# power_supplies.net
KiCad netlist of a schematic drawn in Altium Designer
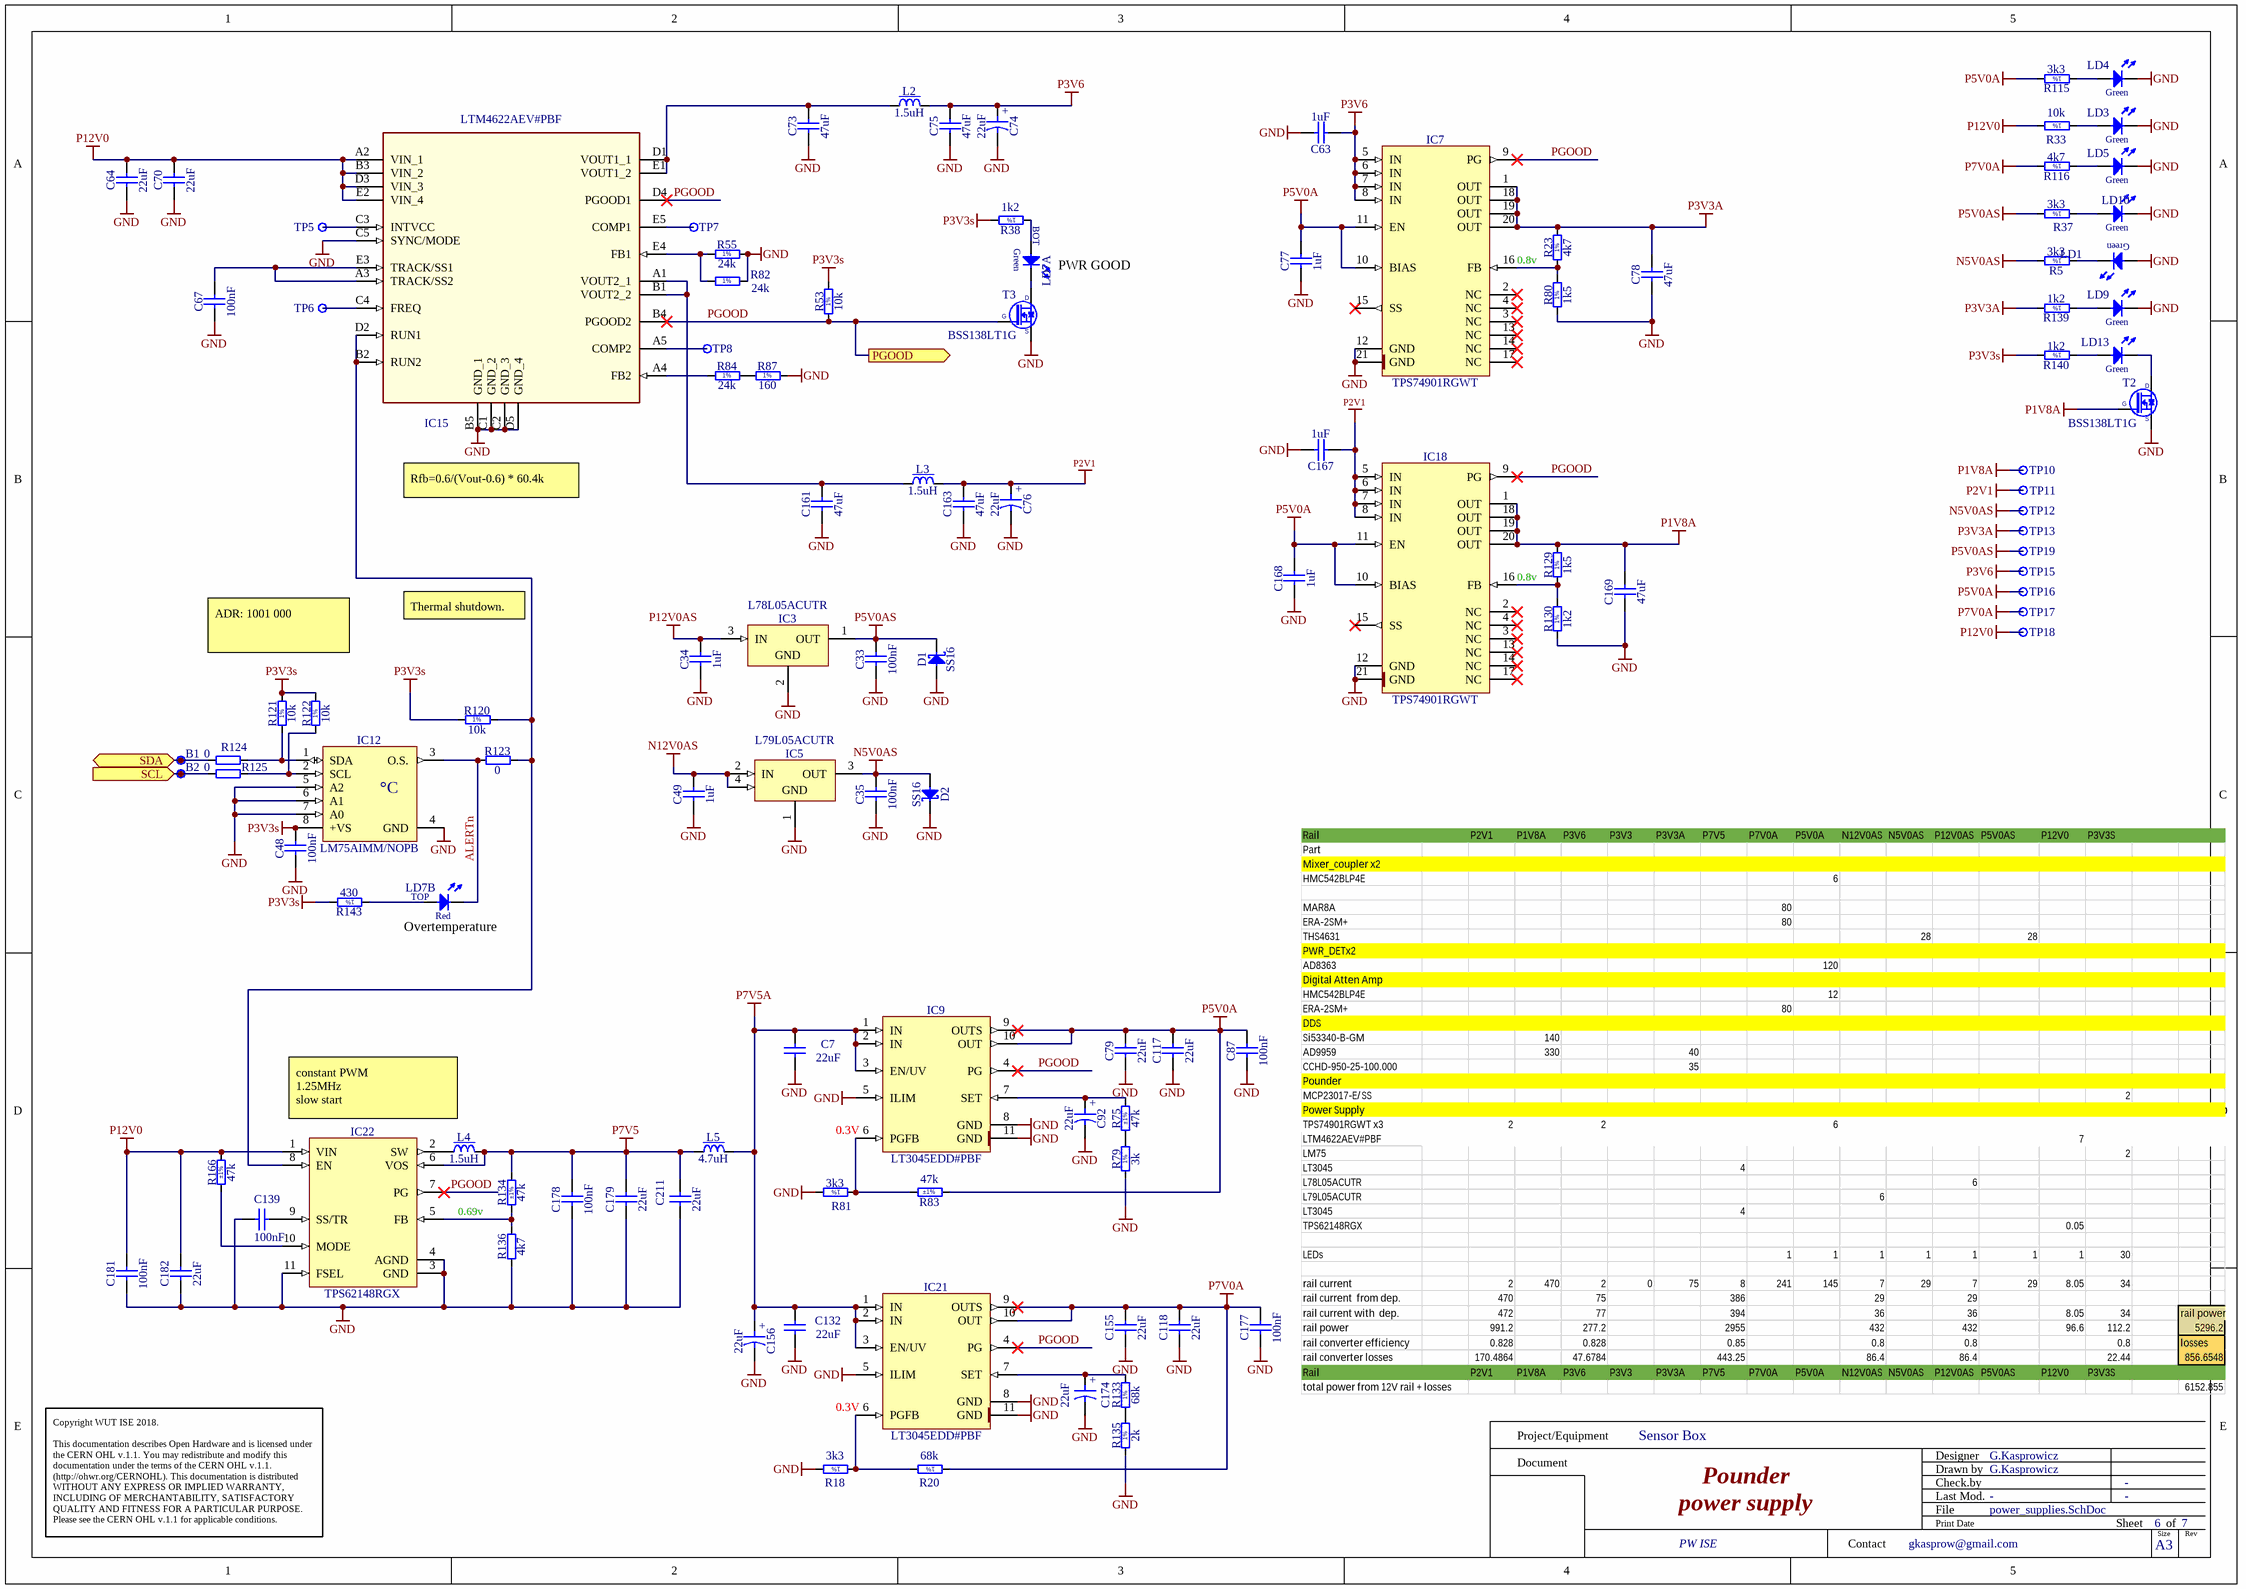
[diagram p0: power_supplies.SchDoc]

(export (version "E")
  (design (tool "Eeschema 10.0.6"))
  (components
    (comp (ref "B1")
      (value "SMD Pad")
      (footprint "C100")
      (description "Through Hole Pad")
      (fields (field (name "PART NUMBER") "SMD_PAD_D1MM") (field (name "AUTHOR") "CERN DEM JLC"))
      (libsource (lib "Eletro-mechanical") (part "Single SMD Pad (Round)"))
    )
    (comp (ref "B2")
      (value "SMD Pad")
      (footprint "C100")
      (description "Through Hole Pad")
      (fields (field (name "PART NUMBER") "SMD_PAD_D1MM") (field (name "AUTHOR") "CERN DEM JLC"))
      (libsource (lib "Eletro-mechanical") (part "Single SMD Pad (Round)"))
    )
    (comp (ref "C7")
      (value "22uF")
      (footprint "CAPC2012X135N")
      (description "Non-polarised capacitor")
      (fields
        (field (name "PART NUMBER") "CC0805_22UF_16V_10%_X5R")
        (field (name "VOLTAGE") "16V")
        (field (name "AUTHOR") "CERN DEM JLC")
      )
      (libsource (lib "Capacitors") (part "Capacitor - non polarized"))
    )
    (comp (ref "C33")
      (value "100nF")
      (footprint "CAPC1005X55N")
      (description "Non-polarised capacitor")
      (fields
        (field (name "PART NUMBER") "CC0402_100NF_16V_10%_X5R")
        (field (name "VOLTAGE") "16V")
        (field (name "AUTHOR") "CERN DEM JLC")
      )
      (libsource (lib "Capacitors") (part "Capacitor - non polarized"))
    )
    (comp (ref "C34")
      (value "1uF")
      (footprint "CAPC1005X55N")
      (description "Non-polarised capacitor")
      (fields
        (field (name "PART NUMBER") "CC0402_1UF_16V_10%_X5R")
        (field (name "VOLTAGE") "16V")
        (field (name "AUTHOR") "CERN DEM JLC")
      )
      (libsource (lib "Capacitors") (part "Capacitor - non polarized"))
    )
    (comp (ref "C35")
      (value "100nF")
      (footprint "CAPC1005X55N")
      (description "Non-polarised capacitor")
      (fields
        (field (name "PART NUMBER") "CC0402_100NF_16V_10%_X5R")
        (field (name "VOLTAGE") "16V")
        (field (name "AUTHOR") "CERN DEM JLC")
      )
      (libsource (lib "Capacitors") (part "Capacitor - non polarized"))
    )
    (comp (ref "C48")
      (value "100nF")
      (footprint "CAPC1005X55N")
      (description "Non-polarised capacitor")
      (fields
        (field (name "PART NUMBER") "CC0402_100NF_16V_10%_X5R")
        (field (name "VOLTAGE") "16V")
        (field (name "AUTHOR") "CERN DEM JLC")
      )
      (libsource (lib "Capacitors") (part "Capacitor - non polarized"))
    )
    (comp (ref "C49")
      (value "1uF")
      (footprint "CAPC1005X55N")
      (description "Non-polarised capacitor")
      (fields
        (field (name "PART NUMBER") "CC0402_1UF_16V_10%_X5R")
        (field (name "VOLTAGE") "16V")
        (field (name "AUTHOR") "CERN DEM JLC")
      )
      (libsource (lib "Capacitors") (part "Capacitor - non polarized"))
    )
    (comp (ref "C63")
      (value "1uF")
      (footprint "CAPC1005X55N")
      (description "Non-polarised capacitor")
      (fields
        (field (name "PART NUMBER") "CC0402_1UF_16V_10%_X5R")
        (field (name "VOLTAGE") "16V")
        (field (name "AUTHOR") "CERN DEM JLC")
      )
      (libsource (lib "Capacitors") (part "Capacitor - non polarized"))
    )
    (comp (ref "C64")
      (value "22uF")
      (footprint "CAPC2012X135N")
      (description "Non-polarised capacitor")
      (fields
        (field (name "PART NUMBER") "CC0805_22UF_16V_10%_X5R")
        (field (name "VOLTAGE") "16V")
        (field (name "AUTHOR") "CERN DEM JLC")
      )
      (libsource (lib "Capacitors") (part "Capacitor - non polarized"))
    )
    (comp (ref "C67")
      (value "100nF")
      (footprint "CAPC1005X55N")
      (description "Non-polarised capacitor")
      (fields
        (field (name "PART NUMBER") "CC0402_100NF_16V_10%_X5R")
        (field (name "VOLTAGE") "16V")
        (field (name "AUTHOR") "CERN DEM JLC")
      )
      (libsource (lib "Capacitors") (part "Capacitor - non polarized"))
    )
    (comp (ref "C70")
      (value "22uF")
      (footprint "CAPC2012X135N")
      (description "Non-polarised capacitor")
      (fields
        (field (name "PART NUMBER") "CC0805_22UF_16V_10%_X5R")
        (field (name "VOLTAGE") "16V")
        (field (name "AUTHOR") "CERN DEM JLC")
      )
      (libsource (lib "Capacitors") (part "Capacitor - non polarized"))
    )
    (comp (ref "C73")
      (value "47uF")
      (footprint "CAPC3225X270N")
      (description "Non-polarised capacitor")
      (fields
        (field (name "PART NUMBER") "CC1210_47UF_10V_20%_X5R")
        (field (name "VOLTAGE") "10V")
        (field (name "AUTHOR") "CERN DEM JLC")
      )
      (libsource (lib "Capacitors") (part "Capacitor - non polarized"))
    )
    (comp (ref "C74")
      (value "22uF")
      (footprint "CAPMP3528X210N")
      (description "Polarised capacitor")
      (fields
        (field (name "PART NUMBER") "CTE3528-21_22UF_10V_10%_LESR0700")
        (field (name "VOLTAGE") "10V")
        (field (name "AUTHOR") "CERN DEM JLC")
      )
      (libsource (lib "Capacitors") (part "Capacitor - polarized"))
    )
    (comp (ref "C75")
      (value "47uF")
      (footprint "CAPC3225X270N")
      (description "Non-polarised capacitor")
      (fields
        (field (name "PART NUMBER") "CC1210_47UF_10V_20%_X5R")
        (field (name "VOLTAGE") "10V")
        (field (name "AUTHOR") "CERN DEM JLC")
      )
      (libsource (lib "Capacitors") (part "Capacitor - non polarized"))
    )
    (comp (ref "C76")
      (value "22uF")
      (footprint "CAPMP3528X210N")
      (description "Polarised capacitor")
      (fields
        (field (name "PART NUMBER") "CTE3528-21_22UF_10V_10%_LESR0700")
        (field (name "VOLTAGE") "10V")
        (field (name "AUTHOR") "CERN DEM JLC")
      )
      (libsource (lib "Capacitors") (part "Capacitor - polarized"))
    )
    (comp (ref "C77")
      (value "1uF")
      (footprint "CAPC1005X55N")
      (description "Non-polarised capacitor")
      (fields
        (field (name "PART NUMBER") "CC0402_1UF_16V_10%_X5R")
        (field (name "VOLTAGE") "16V")
        (field (name "AUTHOR") "CERN DEM JLC")
      )
      (libsource (lib "Capacitors") (part "Capacitor - non polarized"))
    )
    (comp (ref "C78")
      (value "47uF")
      (footprint "CAPC3225X270N")
      (description "Non-polarised capacitor")
      (fields
        (field (name "PART NUMBER") "CC1210_47UF_10V_20%_X5R")
        (field (name "VOLTAGE") "10V")
        (field (name "AUTHOR") "CERN DEM JLC")
      )
      (libsource (lib "Capacitors") (part "Capacitor - non polarized"))
    )
    (comp (ref "C79")
      (value "22uF")
      (footprint "CAPC2012X135N")
      (description "Non-polarised capacitor")
      (fields
        (field (name "PART NUMBER") "CC0805_22UF_16V_10%_X5R")
        (field (name "VOLTAGE") "16V")
        (field (name "AUTHOR") "CERN DEM JLC")
      )
      (libsource (lib "Capacitors") (part "Capacitor - non polarized"))
    )
    (comp (ref "C87")
      (value "100nF")
      (footprint "CAPC1005X55N")
      (description "Non-polarised capacitor")
      (fields
        (field (name "PART NUMBER") "CC0402_100NF_16V_10%_X5R")
        (field (name "VOLTAGE") "16V")
        (field (name "AUTHOR") "CERN DEM JLC")
      )
      (libsource (lib "Capacitors") (part "Capacitor - non polarized"))
    )
    (comp (ref "C92")
      (value "22uF")
      (footprint "CAPMP3528X210N")
      (description "Polarised capacitor")
      (fields
        (field (name "PART NUMBER") "CTE3528-21_22UF_10V_10%_LESR0700")
        (field (name "VOLTAGE") "10V")
        (field (name "AUTHOR") "CERN DEM JLC")
      )
      (libsource (lib "Capacitors") (part "Capacitor - polarized"))
    )
    (comp (ref "C117")
      (value "22uF")
      (footprint "CAPC2012X135N")
      (description "Non-polarised capacitor")
      (fields
        (field (name "PART NUMBER") "CC0805_22UF_16V_10%_X5R")
        (field (name "VOLTAGE") "16V")
        (field (name "AUTHOR") "CERN DEM JLC")
      )
      (libsource (lib "Capacitors") (part "Capacitor - non polarized"))
    )
    (comp (ref "C118")
      (value "22uF")
      (footprint "CAPC2012X135N")
      (description "Non-polarised capacitor")
      (fields
        (field (name "PART NUMBER") "CC0805_22UF_16V_10%_X5R")
        (field (name "VOLTAGE") "16V")
        (field (name "AUTHOR") "CERN DEM JLC")
      )
      (libsource (lib "Capacitors") (part "Capacitor - non polarized"))
    )
    (comp (ref "C132")
      (value "22uF")
      (footprint "CAPC2012X135N")
      (description "Non-polarised capacitor")
      (fields
        (field (name "PART NUMBER") "CC0805_22UF_16V_10%_X5R")
        (field (name "VOLTAGE") "16V")
        (field (name "AUTHOR") "CERN DEM JLC")
      )
      (libsource (lib "Capacitors") (part "Capacitor - non polarized"))
    )
    (comp (ref "C139")
      (value "100nF")
      (footprint "CAPC1005X55N")
      (description "Non-polarised capacitor")
      (fields
        (field (name "PART NUMBER") "CC0402_100NF_16V_10%_X5R")
        (field (name "VOLTAGE") "16V")
        (field (name "AUTHOR") "CERN DEM JLC")
      )
      (libsource (lib "Capacitors") (part "Capacitor - non polarized"))
    )
    (comp (ref "C155")
      (value "22uF")
      (footprint "CAPC2012X135N")
      (description "Non-polarised capacitor")
      (fields
        (field (name "PART NUMBER") "CC0805_22UF_16V_10%_X5R")
        (field (name "VOLTAGE") "16V")
        (field (name "AUTHOR") "CERN DEM JLC")
      )
      (libsource (lib "Capacitors") (part "Capacitor - non polarized"))
    )
    (comp (ref "C156")
      (value "22uF")
      (footprint "CAPMP3528X210N")
      (description "Polarised capacitor")
      (fields
        (field (name "PART NUMBER") "CTE3528-21_22UF_10V_10%_LESR0700")
        (field (name "VOLTAGE") "10V")
        (field (name "AUTHOR") "CERN DEM JLC")
      )
      (libsource (lib "Capacitors") (part "Capacitor - polarized"))
    )
    (comp (ref "C161")
      (value "47uF")
      (footprint "CAPC3225X270N")
      (description "Non-polarised capacitor")
      (fields
        (field (name "PART NUMBER") "CC1210_47UF_10V_20%_X5R")
        (field (name "VOLTAGE") "10V")
        (field (name "AUTHOR") "CERN DEM JLC")
      )
      (libsource (lib "Capacitors") (part "Capacitor - non polarized"))
    )
    (comp (ref "C163")
      (value "47uF")
      (footprint "CAPC3225X270N")
      (description "Non-polarised capacitor")
      (fields
        (field (name "PART NUMBER") "CC1210_47UF_10V_20%_X5R")
        (field (name "VOLTAGE") "10V")
        (field (name "AUTHOR") "CERN DEM JLC")
      )
      (libsource (lib "Capacitors") (part "Capacitor - non polarized"))
    )
    (comp (ref "C167")
      (value "1uF")
      (footprint "CAPC1005X55N")
      (description "Non-polarised capacitor")
      (fields
        (field (name "PART NUMBER") "CC0402_1UF_16V_10%_X5R")
        (field (name "VOLTAGE") "16V")
        (field (name "AUTHOR") "CERN DEM JLC")
      )
      (libsource (lib "Capacitors") (part "Capacitor - non polarized"))
    )
    (comp (ref "C168")
      (value "1uF")
      (footprint "CAPC1005X55N")
      (description "Non-polarised capacitor")
      (fields
        (field (name "PART NUMBER") "CC0402_1UF_16V_10%_X5R")
        (field (name "VOLTAGE") "16V")
        (field (name "AUTHOR") "CERN DEM JLC")
      )
      (libsource (lib "Capacitors") (part "Capacitor - non polarized"))
    )
    (comp (ref "C169")
      (value "47uF")
      (footprint "CAPC3225X270N")
      (description "Non-polarised capacitor")
      (fields
        (field (name "PART NUMBER") "CC1210_47UF_10V_20%_X5R")
        (field (name "VOLTAGE") "10V")
        (field (name "AUTHOR") "CERN DEM JLC")
      )
      (libsource (lib "Capacitors") (part "Capacitor - non polarized"))
    )
    (comp (ref "C174")
      (value "22uF")
      (footprint "CAPMP3528X210N")
      (description "Polarised capacitor")
      (fields
        (field (name "PART NUMBER") "CTE3528-21_22UF_10V_10%_LESR0700")
        (field (name "VOLTAGE") "10V")
        (field (name "AUTHOR") "CERN DEM JLC")
      )
      (libsource (lib "Capacitors") (part "Capacitor - polarized"))
    )
    (comp (ref "C177")
      (value "100nF")
      (footprint "CAPC1005X55N")
      (description "Non-polarised capacitor")
      (fields
        (field (name "PART NUMBER") "CC0402_100NF_16V_10%_X5R")
        (field (name "VOLTAGE") "16V")
        (field (name "AUTHOR") "CERN DEM JLC")
      )
      (libsource (lib "Capacitors") (part "Capacitor - non polarized"))
    )
    (comp (ref "C178")
      (value "100nF")
      (footprint "CAPC1005X55N")
      (description "Non-polarised capacitor")
      (fields
        (field (name "PART NUMBER") "CC0402_100NF_16V_10%_X5R")
        (field (name "VOLTAGE") "16V")
        (field (name "AUTHOR") "CERN DEM JLC")
      )
      (libsource (lib "Capacitors") (part "Capacitor - non polarized"))
    )
    (comp (ref "C179")
      (value "22uF")
      (footprint "CAPC2012X135N")
      (description "Non-polarised capacitor")
      (fields
        (field (name "PART NUMBER") "CC0805_22UF_16V_10%_X5R")
        (field (name "VOLTAGE") "16V")
        (field (name "AUTHOR") "CERN DEM JLC")
      )
      (libsource (lib "Capacitors") (part "Capacitor - non polarized"))
    )
    (comp (ref "C181")
      (value "100nF")
      (footprint "CAPC1005X55N")
      (description "Non-polarised capacitor")
      (fields
        (field (name "PART NUMBER") "CC0402_100NF_16V_10%_X5R")
        (field (name "VOLTAGE") "16V")
        (field (name "AUTHOR") "CERN DEM JLC")
      )
      (libsource (lib "Capacitors") (part "Capacitor - non polarized"))
    )
    (comp (ref "C182")
      (value "22uF")
      (footprint "CAPC2012X135N")
      (description "Non-polarised capacitor")
      (fields
        (field (name "PART NUMBER") "CC0805_22UF_16V_10%_X5R")
        (field (name "VOLTAGE") "16V")
        (field (name "AUTHOR") "CERN DEM JLC")
      )
      (libsource (lib "Capacitors") (part "Capacitor - non polarized"))
    )
    (comp (ref "C211")
      (value "22uF")
      (footprint "CAPC2012X135N")
      (description "Non-polarised capacitor")
      (fields
        (field (name "PART NUMBER") "CC0805_22UF_16V_10%_X5R")
        (field (name "VOLTAGE") "16V")
        (field (name "AUTHOR") "CERN DEM JLC")
      )
      (libsource (lib "Capacitors") (part "Capacitor - non polarized"))
    )
    (comp (ref "D1")
      (value "SS16")
      (footprint "DIOM5127X229N")
      (description "Schottky Diode")
      (fields
        (field (name "VOLTAGE") "60V")
        (field (name "POWER") "1A")
        (field (name "AUTHOR") "CERN DEM JLC")
      )
      (libsource (lib "ICs And Semiconductors") (part "Diode Schottky"))
    )
    (comp (ref "D2")
      (value "SS16")
      (footprint "DIOM5127X229N")
      (description "Schottky Diode")
      (fields
        (field (name "VOLTAGE") "60V")
        (field (name "POWER") "1A")
        (field (name "AUTHOR") "CERN DEM JLC")
      )
      (libsource (lib "ICs And Semiconductors") (part "Diode Schottky"))
    )
    (comp (ref "IC3")
      (value "L78L05ACUTR")
      (footprint "SOT89")
      (description "3-Terminal Regulator 1=OUT 2=GND 3=IN")
      (fields (field (name "MANUFACTURER") "ST MICROELECTRONICS") (field (name "AUTHOR") "CERN DEM JLC"))
      (libsource (lib "ICs And Semiconductors") (part "REG3 1OUT-2GND-3IN"))
    )
    (comp (ref "IC5")
      (value "L79L05ACUTR")
      (footprint "SOT89")
      (description "3-Terminal Regulator 1=GND 2=IN 3=OUT 4=IN")
      (fields (field (name "MANUFACTURER") "ST MICROELECTRONICS") (field (name "AUTHOR") "CERN DEM JLC"))
      (libsource (lib "ICs And Semiconductors") (part "REG3+1 1GND-2IN-3OUT+4IN"))
    )
    (comp (ref "IC7")
      (value "TPS74901RGWT")
      (footprint "QFN65P500X500X100-21N-S325")
      (description "3A, 0.8 to 3.6V Adjustable Low-Dropout Linear Regulator with Programmable Soft-Start")
      (fields (field (name "MANUFACTURER") "TEXAS INSTRUMENTS") (field (name "AUTHOR") "CERN DEM JLC"))
      (libsource (lib "ICs And Semiconductors") (part "TPS74901RGWT"))
    )
    (comp (ref "IC9")
      (value "LT3045EDD#PBF")
      (footprint "SON50P300X300X80-11N-R175X248")
      (description "20V, 500mA, Ultralow Noise, Ultrahigh PSRR Linear Regulator")
      (fields (field (name "MANUFACTURER") "LINEAR TECHNOLOGY") (field (name "AUTHOR") "CERN DEM JLC"))
      (libsource (lib "ICs And Semiconductors") (part "LT3045EDD"))
    )
    (comp (ref "IC12")
      (value "LM75AIMM/NOPB")
      (footprint "SOP65P490X109-8N")
      (description "Digital Temperature Sensor and Thermal Watchdog with Two-Wire Interface")
      (fields (field (name "MANUFACTURER") "TEXAS INSTRUMENTS") (field (name "AUTHOR") "CERN DEM JLC"))
      (libsource (lib "ICs And Semiconductors") (part "LM75"))
    )
    (comp (ref "IC15")
      (value "LTM4622AEV#PBF")
      (footprint "LGA25C127P5X5_625X625X190")
      (description "Dual Ultrathin 2A or Single 4A, 3.6V to 20V, 1.5V to 12V   Step-Down DC/DC μModule Regulator")
      (fields (field (name "MANUFACTURER") "LINEAR TECHNOLOGY") (field (name "AUTHOR") "GK"))
      (libsource (lib "LIBRARY_SCH") (part "PM_LTM4622"))
    )
    (comp (ref "IC18")
      (value "TPS74901RGWT")
      (footprint "QFN65P500X500X100-21N-S325")
      (description "3A, 0.8 to 3.6V Adjustable Low-Dropout Linear Regulator with Programmable Soft-Start")
      (fields (field (name "MANUFACTURER") "TEXAS INSTRUMENTS") (field (name "AUTHOR") "CERN DEM JLC"))
      (libsource (lib "ICs And Semiconductors") (part "TPS74901RGWT"))
    )
    (comp (ref "IC21")
      (value "LT3045EDD#PBF")
      (footprint "SON50P300X300X80-11N-R175X248")
      (description "20V, 500mA, Ultralow Noise, Ultrahigh PSRR Linear Regulator")
      (fields (field (name "MANUFACTURER") "LINEAR TECHNOLOGY") (field (name "AUTHOR") "CERN DEM JLC"))
      (libsource (lib "ICs And Semiconductors") (part "LT3045EDD"))
    )
    (comp (ref "IC22")
      (value "TPS62148RGX")
      (footprint "TEXAS_RGX0011A")
      (description "3V-17V 2A Step-Down Converter, High Accuracy, With DCS-Control")
      (fields (field (name "MANUFACTURER") "TEXAS INSTRUMENTS") (field (name "AUTHOR") "CERN DEM MR"))
      (libsource (lib "ICs And Semiconductors") (part "TPS62148"))
    )
    (comp (ref "L2")
      (value "1.5uH")
      (footprint "IND_TDK_SPM6530")
      (description "Inductor With Core")
      (fields
        (field (name "PART NUMBER") "IND_1.5UH_20%_TDK_SPM6530")
        (field (name "POWER") "11A")
        (field (name "AUTHOR") "CERN DEM MR")
      )
      (libsource (lib "Inductors & Transformers") (part "Inductor With Magnetic core"))
    )
    (comp (ref "L3")
      (value "1.5uH")
      (footprint "IND_TDK_SPM6530")
      (description "Inductor With Core")
      (fields
        (field (name "PART NUMBER") "IND_1.5UH_20%_TDK_SPM6530")
        (field (name "POWER") "11A")
        (field (name "AUTHOR") "CERN DEM MR")
      )
      (libsource (lib "Inductors & Transformers") (part "Inductor With Magnetic core"))
    )
    (comp (ref "L4")
      (value "1.5uH")
      (footprint "IND_TDK_SPM6530")
      (description "Inductor With Core")
      (fields
        (field (name "PART NUMBER") "IND_1.5UH_20%_TDK_SPM6530")
        (field (name "POWER") "11A")
        (field (name "AUTHOR") "CERN DEM MR")
      )
      (libsource (lib "Inductors & Transformers") (part "Inductor With Magnetic core"))
    )
    (comp (ref "L5")
      (value "4.7uH")
      (footprint "IND_WURTH_WE-TPC-2813")
      (description "Inductor With Core")
      (fields
        (field (name "PART NUMBER") "IND_4.7UH_30%_WURTH_WE-TPC_744029004")
        (field (name "POWER") "1A")
        (field (name "AUTHOR") "CERN DEM JLC")
      )
      (libsource (lib "Inductors & Transformers") (part "Inductor With Magnetic core"))
    )
    (comp (ref "LD1")
      (value "Green")
      (footprint "LED_KINGBRIGHT_KPH-1608CGCKr")
      (description "Green 0603")
      (fields
        (field (name "PART NUMBER") "LED_KINGBRIGHT_KPH-1608CGCK")
        (field (name "MANUFACTURER") "KINGBRIGHT")
        (field (name "AUTHOR") "CERN DEM JLC")
      )
      (libsource (lib "LIBRARY_SCH") (part "LED_0603_Green"))
    )
    (comp (ref "LD3")
      (value "Green")
      (footprint "LED_KINGBRIGHT_KPH-1608CGCKr")
      (description "Green 0603")
      (fields
        (field (name "PART NUMBER") "LED_KINGBRIGHT_KPH-1608CGCK")
        (field (name "MANUFACTURER") "KINGBRIGHT")
        (field (name "AUTHOR") "CERN DEM JLC")
      )
      (libsource (lib "LIBRARY_SCH") (part "LED_0603_Green"))
    )
    (comp (ref "LD4")
      (value "Green")
      (footprint "LED_KINGBRIGHT_KPH-1608CGCKr")
      (description "Green 0603")
      (fields
        (field (name "PART NUMBER") "LED_KINGBRIGHT_KPH-1608CGCK")
        (field (name "MANUFACTURER") "KINGBRIGHT")
        (field (name "AUTHOR") "CERN DEM JLC")
      )
      (libsource (lib "LIBRARY_SCH") (part "LED_0603_Green"))
    )
    (comp (ref "LD5")
      (value "Green")
      (footprint "LED_KINGBRIGHT_KPH-1608CGCKr")
      (description "Green 0603")
      (fields
        (field (name "PART NUMBER") "LED_KINGBRIGHT_KPH-1608CGCK")
        (field (name "MANUFACTURER") "KINGBRIGHT")
        (field (name "AUTHOR") "CERN DEM JLC")
      )
      (libsource (lib "LIBRARY_SCH") (part "LED_0603_Green"))
    )
    (comp (ref "LD7")
      (value "Red/Green")
      (footprint "LED_DIALIGHT_571-0112F")
      (description "2x LED  Botom Green, Top Red")
      (fields
        (field (name "PART NUMBER") "LED_DIALIGHT_571-0112F")
        (field (name "MANUFACTURER") "DIALIGHT")
        (field (name "AUTHOR") "CERN DEM JLC")
      )
      (libsource (lib "ICs And Semiconductors") (part "LED x2 G-1C2A-BOT_R-3C4A-TOP"))
    )
    (comp (ref "LD9")
      (value "Green")
      (footprint "LED_KINGBRIGHT_KPH-1608CGCKr")
      (description "Green 0603")
      (fields
        (field (name "PART NUMBER") "LED_KINGBRIGHT_KPH-1608CGCK")
        (field (name "MANUFACTURER") "KINGBRIGHT")
        (field (name "AUTHOR") "CERN DEM JLC")
      )
      (libsource (lib "LIBRARY_SCH") (part "LED_0603_Green"))
    )
    (comp (ref "LD10")
      (value "Green")
      (footprint "LED_KINGBRIGHT_KPH-1608CGCKr")
      (description "Green 0603")
      (fields
        (field (name "PART NUMBER") "LED_KINGBRIGHT_KPH-1608CGCK")
        (field (name "MANUFACTURER") "KINGBRIGHT")
        (field (name "AUTHOR") "CERN DEM JLC")
      )
      (libsource (lib "LIBRARY_SCH") (part "LED_0603_Green"))
    )
    (comp (ref "LD13")
      (value "Green")
      (footprint "LED_KINGBRIGHT_KPH-1608CGCKr")
      (description "Green 0603")
      (fields
        (field (name "PART NUMBER") "LED_KINGBRIGHT_KPH-1608CGCK")
        (field (name "MANUFACTURER") "KINGBRIGHT")
        (field (name "AUTHOR") "CERN DEM JLC")
      )
      (libsource (lib "LIBRARY_SCH") (part "LED_0603_Green"))
    )
    (comp (ref "R5")
      (value "3k3")
      (footprint "RESC1608X55N")
      (description "Resistor - 1%")
      (fields
        (field (name "PART NUMBER") "R0603_3K3_1%_0.1W_100PPM")
        (field (name "POWER") "0.1W")
        (field (name "AUTHOR") "CERN DEM JLC")
      )
      (libsource (lib "Resistors") (part "Resistor - 1%"))
    )
    (comp (ref "R18")
      (value "3k3")
      (footprint "RESC1608X55N")
      (description "Resistor - 1%")
      (fields
        (field (name "PART NUMBER") "R0603_3K3_1%_0.1W_100PPM")
        (field (name "POWER") "0.1W")
        (field (name "AUTHOR") "CERN DEM JLC")
      )
      (libsource (lib "Resistors") (part "Resistor - 1%"))
    )
    (comp (ref "R20")
      (value "68k")
      (footprint "RESC1005X40N")
      (description "Resistor - 1%")
      (fields
        (field (name "PART NUMBER") "R0402_68K_1%_0.0625W_100PPM")
        (field (name "POWER") "0.0625W")
        (field (name "AUTHOR") "CERN DEM JLC")
      )
      (libsource (lib "Resistors") (part "Resistor - 1%"))
    )
    (comp (ref "R23")
      (value "4k7")
      (footprint "RESC1608X55N")
      (description "Resistor - 1%")
      (fields
        (field (name "PART NUMBER") "R0603_4K7_1%_0.1W_100PPM")
        (field (name "POWER") "0.1W")
        (field (name "AUTHOR") "CERN DEM JLC")
      )
      (libsource (lib "Resistors") (part "Resistor - 1%"))
    )
    (comp (ref "R33")
      (value "10k")
      (footprint "RESC1005X40N")
      (description "Resistor - 1%")
      (fields
        (field (name "PART NUMBER") "R0402_10K_1%_0.0625W_100PPM")
        (field (name "POWER") "0.0625W")
        (field (name "AUTHOR") "CERN DEM JLC")
      )
      (libsource (lib "Resistors") (part "Resistor - 1%"))
    )
    (comp (ref "R37")
      (value "3k3")
      (footprint "RESC1608X55N")
      (description "Resistor - 1%")
      (fields
        (field (name "PART NUMBER") "R0603_3K3_1%_0.1W_100PPM")
        (field (name "POWER") "0.1W")
        (field (name "AUTHOR") "CERN DEM JLC")
      )
      (libsource (lib "Resistors") (part "Resistor - 1%"))
    )
    (comp (ref "R38")
      (value "1k2")
      (footprint "RESC1608X55N")
      (description "Resistor - 1%")
      (fields
        (field (name "PART NUMBER") "R0603_1K2_1%_0.1W_100PPM")
        (field (name "POWER") "0.1W")
        (field (name "AUTHOR") "CERN DEM JLC")
      )
      (libsource (lib "Resistors") (part "Resistor - 1%"))
    )
    (comp (ref "R53")
      (value "10k")
      (footprint "RESC1005X40N")
      (description "Resistor - 1%")
      (fields
        (field (name "PART NUMBER") "R0402_10K_1%_0.0625W_100PPM")
        (field (name "POWER") "0.0625W")
        (field (name "AUTHOR") "CERN DEM JLC")
      )
      (libsource (lib "Resistors") (part "Resistor - 1%"))
    )
    (comp (ref "R55")
      (value "24k")
      (footprint "RESC1608X55N")
      (description "Resistor - 1%")
      (fields
        (field (name "PART NUMBER") "R0603_24K_1%_0.1W_100PPM")
        (field (name "POWER") "0.1W")
        (field (name "AUTHOR") "CERN DEM JLC")
      )
      (libsource (lib "Resistors") (part "Resistor - 1%"))
    )
    (comp (ref "R75")
      (value "47k")
      (footprint "RESC1005X40N")
      (description "Resistor - 1%")
      (fields
        (field (name "TOLERANCE") "±1%")
        (field (name "PART NUMBER") "R0402_47K_1%_0.0625W_100PPM")
        (field (name "POWER") "0.0625W")
        (field (name "AUTHOR") "CERN DEM JLC")
      )
      (libsource (lib "") (part "Resistor - 1%_1"))
    )
    (comp (ref "R79")
      (value "3k")
      (footprint "RESC1005X40N")
      (description "Resistor - 1%")
      (fields
        (field (name "PART NUMBER") "R0402_3K_1%_0.0625W_100PPM")
        (field (name "POWER") "0.0625W")
        (field (name "AUTHOR") "CERN DEM JLC")
      )
      (libsource (lib "Resistors") (part "Resistor - 1%"))
    )
    (comp (ref "R80")
      (value "1k5")
      (footprint "RESC1608X55N")
      (description "Resistor - 1%")
      (fields
        (field (name "PART NUMBER") "R0603_1K5_1%_0.1W_100PPM")
        (field (name "POWER") "0.1W")
        (field (name "AUTHOR") "CERN DEM JLC")
      )
      (libsource (lib "Resistors") (part "Resistor - 1%"))
    )
    (comp (ref "R81")
      (value "3k3")
      (footprint "RESC1608X55N")
      (description "Resistor - 1%")
      (fields
        (field (name "PART NUMBER") "R0603_3K3_1%_0.1W_100PPM")
        (field (name "POWER") "0.1W")
        (field (name "AUTHOR") "CERN DEM JLC")
      )
      (libsource (lib "Resistors") (part "Resistor - 1%"))
    )
    (comp (ref "R82")
      (value "24k")
      (footprint "RESC1608X55N")
      (description "Resistor - 1%")
      (fields
        (field (name "PART NUMBER") "R0603_24K_1%_0.1W_100PPM")
        (field (name "POWER") "0.1W")
        (field (name "AUTHOR") "CERN DEM JLC")
      )
      (libsource (lib "Resistors") (part "Resistor - 1%"))
    )
    (comp (ref "R83")
      (value "47k")
      (footprint "RESC1005X40N")
      (description "Resistor - 1%")
      (fields
        (field (name "TOLERANCE") "±1%")
        (field (name "PART NUMBER") "R0402_47K_1%_0.0625W_100PPM")
        (field (name "POWER") "0.0625W")
        (field (name "AUTHOR") "CERN DEM JLC")
      )
      (libsource (lib "") (part "Resistor - 1%_1"))
    )
    (comp (ref "R84")
      (value "24k")
      (footprint "RESC1608X55N")
      (description "Resistor - 1%")
      (fields
        (field (name "PART NUMBER") "R0603_24K_1%_0.1W_100PPM")
        (field (name "POWER") "0.1W")
        (field (name "AUTHOR") "CERN DEM JLC")
      )
      (libsource (lib "Resistors") (part "Resistor - 1%"))
    )
    (comp (ref "R87")
      (value "160")
      (footprint "RESC1608X55N")
      (description "Resistor - 1%")
      (fields
        (field (name "PART NUMBER") "R0603_160R_1%_0.1W_100PPM")
        (field (name "POWER") "0.1W")
        (field (name "AUTHOR") "CERN DEM JLC")
      )
      (libsource (lib "Resistors") (part "Resistor - 1%"))
    )
    (comp (ref "R115")
      (value "3k3")
      (footprint "RESC1608X55N")
      (description "Resistor - 1%")
      (fields
        (field (name "PART NUMBER") "R0603_3K3_1%_0.1W_100PPM")
        (field (name "POWER") "0.1W")
        (field (name "AUTHOR") "CERN DEM JLC")
      )
      (libsource (lib "Resistors") (part "Resistor - 1%"))
    )
    (comp (ref "R116")
      (value "4k7")
      (footprint "RESC1608X55N")
      (description "Resistor - 1%")
      (fields
        (field (name "PART NUMBER") "R0603_4K7_1%_0.1W_100PPM")
        (field (name "POWER") "0.1W")
        (field (name "AUTHOR") "CERN DEM JLC")
      )
      (libsource (lib "Resistors") (part "Resistor - 1%"))
    )
    (comp (ref "R120")
      (value "10k")
      (footprint "RESC1005X40N")
      (description "Resistor - 1%")
      (fields
        (field (name "PART NUMBER") "R0402_10K_1%_0.0625W_100PPM")
        (field (name "POWER") "0.0625W")
        (field (name "AUTHOR") "CERN DEM JLC")
      )
      (libsource (lib "Resistors") (part "Resistor - 1%"))
    )
    (comp (ref "R121")
      (value "10k")
      (footprint "RESC1005X40N")
      (description "Resistor - 1%")
      (fields
        (field (name "PART NUMBER") "R0402_10K_1%_0.0625W_100PPM")
        (field (name "POWER") "0.0625W")
        (field (name "AUTHOR") "CERN DEM JLC")
      )
      (libsource (lib "Resistors") (part "Resistor - 1%"))
    )
    (comp (ref "R122")
      (value "10k")
      (footprint "RESC1005X40N")
      (description "Resistor - 1%")
      (fields
        (field (name "PART NUMBER") "R0402_10K_1%_0.0625W_100PPM")
        (field (name "POWER") "0.0625W")
        (field (name "AUTHOR") "CERN DEM JLC")
      )
      (libsource (lib "Resistors") (part "Resistor - 1%"))
    )
    (comp (ref "R123")
      (value "0")
      (footprint "RESC1005X40N")
      (description "Resistor")
      (fields
        (field (name "PART NUMBER") "R0402_0R_JUMPER")
        (field (name "MANUFACTURER") "GENERIC")
        (field (name "AUTHOR") "CERN DEM JLC")
      )
      (libsource (lib "Resistors") (part "Resistor"))
    )
    (comp (ref "R124")
      (value "0")
      (footprint "RESC1005X40N")
      (description "Resistor")
      (fields
        (field (name "PART NUMBER") "R0402_0R_JUMPER")
        (field (name "MANUFACTURER") "GENERIC")
        (field (name "AUTHOR") "CERN DEM JLC")
      )
      (libsource (lib "Resistors") (part "Resistor"))
    )
    (comp (ref "R125")
      (value "0")
      (footprint "RESC1005X40N")
      (description "Resistor")
      (fields
        (field (name "PART NUMBER") "R0402_0R_JUMPER")
        (field (name "MANUFACTURER") "GENERIC")
        (field (name "AUTHOR") "CERN DEM JLC")
      )
      (libsource (lib "Resistors") (part "Resistor"))
    )
    (comp (ref "R129")
      (value "1k5")
      (footprint "RESC1608X55N")
      (description "Resistor - 1%")
      (fields
        (field (name "PART NUMBER") "R0603_1K5_1%_0.1W_100PPM")
        (field (name "POWER") "0.1W")
        (field (name "AUTHOR") "CERN DEM JLC")
      )
      (libsource (lib "Resistors") (part "Resistor - 1%"))
    )
    (comp (ref "R130")
      (value "1k2")
      (footprint "RESC1608X55N")
      (description "Resistor - 1%")
      (fields
        (field (name "PART NUMBER") "R0603_1K2_1%_0.1W_100PPM")
        (field (name "POWER") "0.1W")
        (field (name "AUTHOR") "CERN DEM JLC")
      )
      (libsource (lib "Resistors") (part "Resistor - 1%"))
    )
    (comp (ref "R133")
      (value "68k")
      (footprint "RESC1005X40N")
      (description "Resistor - 1%")
      (fields
        (field (name "PART NUMBER") "R0402_68K_1%_0.0625W_100PPM")
        (field (name "POWER") "0.0625W")
        (field (name "AUTHOR") "CERN DEM JLC")
      )
      (libsource (lib "Resistors") (part "Resistor - 1%"))
    )
    (comp (ref "R134")
      (value "47k")
      (footprint "RESC1005X40N")
      (description "Resistor - 1%")
      (fields
        (field (name "TOLERANCE") "±1%")
        (field (name "PART NUMBER") "R0402_47K_1%_0.0625W_100PPM")
        (field (name "POWER") "0.0625W")
        (field (name "AUTHOR") "CERN DEM JLC")
      )
      (libsource (lib "") (part "Resistor - 1%_1"))
    )
    (comp (ref "R135")
      (value "2k")
      (footprint "RESC1005X40N")
      (description "Resistor - 1%")
      (fields
        (field (name "PART NUMBER") "R0402_2K_1%_0.0625W_100PPM")
        (field (name "POWER") "0.0625W")
        (field (name "AUTHOR") "CERN DEM JLC")
      )
      (libsource (lib "Resistors") (part "Resistor - 1%"))
    )
    (comp (ref "R136")
      (value "4k7")
      (footprint "RESC1608X55N")
      (description "Resistor - 1%")
      (fields
        (field (name "PART NUMBER") "R0603_4K7_1%_0.1W_100PPM")
        (field (name "POWER") "0.1W")
        (field (name "AUTHOR") "CERN DEM JLC")
      )
      (libsource (lib "Resistors") (part "Resistor - 1%"))
    )
    (comp (ref "R139")
      (value "1k2")
      (footprint "RESC1608X55N")
      (description "Resistor - 1%")
      (fields
        (field (name "PART NUMBER") "R0603_1K2_1%_0.1W_100PPM")
        (field (name "POWER") "0.1W")
        (field (name "AUTHOR") "CERN DEM JLC")
      )
      (libsource (lib "Resistors") (part "Resistor - 1%"))
    )
    (comp (ref "R140")
      (value "1k2")
      (footprint "RESC1608X55N")
      (description "Resistor - 1%")
      (fields
        (field (name "PART NUMBER") "R0603_1K2_1%_0.1W_100PPM")
        (field (name "POWER") "0.1W")
        (field (name "AUTHOR") "CERN DEM JLC")
      )
      (libsource (lib "Resistors") (part "Resistor - 1%"))
    )
    (comp (ref "R143")
      (value "430")
      (footprint "RESC1608X55N")
      (description "Resistor - 1%")
      (fields
        (field (name "PART NUMBER") "R0603_430R_1%_0.1W_100PPM")
        (field (name "POWER") "0.1W")
        (field (name "AUTHOR") "CERN DEM JLC")
      )
      (libsource (lib "Resistors") (part "Resistor - 1%"))
    )
    (comp (ref "R166")
      (value "47k")
      (footprint "RESC1005X40N")
      (description "Resistor - 1%")
      (fields
        (field (name "TOLERANCE") "±1%")
        (field (name "PART NUMBER") "R0402_47K_1%_0.0625W_100PPM")
        (field (name "POWER") "0.0625W")
        (field (name "AUTHOR") "CERN DEM JLC")
      )
      (libsource (lib "") (part "Resistor - 1%_1"))
    )
    (comp (ref "T2")
      (value "BSS138LT1G")
      (footprint "SOT95P240X110-3N")
      (description "N-CHANNEL MOSFET WITH DIODE")
      (fields (field (name "MANUFACTURER") "ON SEMICONDUCTOR") (field (name "AUTHOR") "CERN DEM JLC"))
      (libsource (lib "ICs And Semiconductors") (part "N-MOSFET-D 1G 2S 3D"))
    )
    (comp (ref "T3")
      (value "BSS138LT1G")
      (footprint "SOT95P240X110-3N")
      (description "N-CHANNEL MOSFET WITH DIODE")
      (fields (field (name "MANUFACTURER") "ON SEMICONDUCTOR") (field (name "AUTHOR") "CERN DEM JLC"))
      (libsource (lib "ICs And Semiconductors") (part "N-MOSFET-D 1G 2S 3D"))
    )
    (comp (ref "TP5")
      (value "Test Point")
      (footprint "TPS127")
      (fields (field (name "PART NUMBER") "SMD_PAD_1.27X1.27MM") (field (name "AUTHOR") "CERN DEM JLC"))
      (libsource (lib "Eletro-mechanical") (part "Test Point"))
    )
    (comp (ref "TP6")
      (value "Test Point")
      (footprint "TPS127")
      (fields (field (name "PART NUMBER") "SMD_PAD_1.27X1.27MM") (field (name "AUTHOR") "CERN DEM JLC"))
      (libsource (lib "Eletro-mechanical") (part "Test Point"))
    )
    (comp (ref "TP7")
      (value "Test Point")
      (footprint "TPS127")
      (fields (field (name "PART NUMBER") "SMD_PAD_1.27X1.27MM") (field (name "AUTHOR") "CERN DEM JLC"))
      (libsource (lib "Eletro-mechanical") (part "Test Point"))
    )
    (comp (ref "TP8")
      (value "Test Point")
      (footprint "TPS127")
      (fields (field (name "PART NUMBER") "SMD_PAD_1.27X1.27MM") (field (name "AUTHOR") "CERN DEM JLC"))
      (libsource (lib "Eletro-mechanical") (part "Test Point"))
    )
    (comp (ref "TP10")
      (value "Test Point")
      (footprint "TPS127")
      (fields (field (name "PART NUMBER") "SMD_PAD_1.27X1.27MM") (field (name "AUTHOR") "CERN DEM JLC"))
      (libsource (lib "Eletro-mechanical") (part "Test Point"))
    )
    (comp (ref "TP11")
      (value "Test Point")
      (footprint "TPS127")
      (fields (field (name "PART NUMBER") "SMD_PAD_1.27X1.27MM") (field (name "AUTHOR") "CERN DEM JLC"))
      (libsource (lib "Eletro-mechanical") (part "Test Point"))
    )
    (comp (ref "TP12")
      (value "Test Point")
      (footprint "TPS127")
      (fields (field (name "PART NUMBER") "SMD_PAD_1.27X1.27MM") (field (name "AUTHOR") "CERN DEM JLC"))
      (libsource (lib "Eletro-mechanical") (part "Test Point"))
    )
    (comp (ref "TP13")
      (value "Test Point")
      (footprint "TPS127")
      (fields (field (name "PART NUMBER") "SMD_PAD_1.27X1.27MM") (field (name "AUTHOR") "CERN DEM JLC"))
      (libsource (lib "Eletro-mechanical") (part "Test Point"))
    )
    (comp (ref "TP15")
      (value "Test Point")
      (footprint "TPS127")
      (fields (field (name "PART NUMBER") "SMD_PAD_1.27X1.27MM") (field (name "AUTHOR") "CERN DEM JLC"))
      (libsource (lib "Eletro-mechanical") (part "Test Point"))
    )
    (comp (ref "TP16")
      (value "Test Point")
      (footprint "TPS127")
      (fields (field (name "PART NUMBER") "SMD_PAD_1.27X1.27MM") (field (name "AUTHOR") "CERN DEM JLC"))
      (libsource (lib "Eletro-mechanical") (part "Test Point"))
    )
    (comp (ref "TP17")
      (value "Test Point")
      (footprint "TPS127")
      (fields (field (name "PART NUMBER") "SMD_PAD_1.27X1.27MM") (field (name "AUTHOR") "CERN DEM JLC"))
      (libsource (lib "Eletro-mechanical") (part "Test Point"))
    )
    (comp (ref "TP18")
      (value "Test Point")
      (footprint "TPS127")
      (fields (field (name "PART NUMBER") "SMD_PAD_1.27X1.27MM") (field (name "AUTHOR") "CERN DEM JLC"))
      (libsource (lib "Eletro-mechanical") (part "Test Point"))
    )
    (comp (ref "TP19")
      (value "Test Point")
      (footprint "TPS127")
      (fields (field (name "PART NUMBER") "SMD_PAD_1.27X1.27MM") (field (name "AUTHOR") "CERN DEM JLC"))
      (libsource (lib "Eletro-mechanical") (part "Test Point"))
    )
  )
  (nets
    (net (code "1") (name "/ALERTn") (class "Default")
      (node (ref "IC12") (pin "3") (pinfunction "O.S._3") (pintype "output"))
      (node (ref "LD7") (pin "3") (pinfunction "C_3") (pintype "passive"))
      (node (ref "R123") (pin "1") (pinfunction "1_1") (pintype "passive"))
    )
    (net (code "2") (name "/PGOOD") (class "Default")
      (node (ref "IC15") (pin "B4") (pinfunction "PGOOD2_B4") (pintype "open_collector"))
      (node (ref "IC15") (pin "D4") (pinfunction "PGOOD1_D4") (pintype "open_collector"))
      (node (ref "IC18") (pin "9") (pinfunction "PG_9") (pintype "output"))
      (node (ref "IC21") (pin "4") (pinfunction "PG_4") (pintype "output"))
      (node (ref "IC22") (pin "7") (pinfunction "PG_7") (pintype "output"))
      (node (ref "IC7") (pin "9") (pinfunction "PG_9") (pintype "output"))
      (node (ref "IC9") (pin "4") (pinfunction "PG_4") (pintype "output"))
      (node (ref "R53") (pin "1") (pinfunction "1_1") (pintype "passive"))
      (node (ref "T3") (pin "1") (pinfunction "G_1") (pintype "passive"))
    )
    (net (code "3") (name "/SCL") (class "Default")
      (node (ref "B2") (pin "1") (pinfunction "1_1") (pintype "bidirectional"))
      (node (ref "R125") (pin "1") (pinfunction "1_1") (pintype "passive"))
    )
    (net (code "4") (name "/SDA") (class "Default")
      (node (ref "B1") (pin "1") (pinfunction "1_1") (pintype "bidirectional"))
      (node (ref "R124") (pin "1") (pinfunction "1_1") (pintype "passive"))
    )
    (net (code "5") (name "GND") (class "Default")
      (node (ref "C117") (pin "1") (pinfunction "1_1") (pintype "passive"))
      (node (ref "C118") (pin "1") (pinfunction "1_1") (pintype "passive"))
      (node (ref "C132") (pin "1") (pinfunction "1_1") (pintype "passive"))
      (node (ref "C139") (pin "2") (pinfunction "2_2") (pintype "passive"))
      (node (ref "C155") (pin "1") (pinfunction "1_1") (pintype "passive"))
      (node (ref "C156") (pin "2") (pinfunction "2_2") (pintype "passive"))
      (node (ref "C161") (pin "1") (pinfunction "1_1") (pintype "passive"))
      (node (ref "C163") (pin "1") (pinfunction "1_1") (pintype "passive"))
      (node (ref "C167") (pin "2") (pinfunction "2_2") (pintype "passive"))
      (node (ref "C168") (pin "1") (pinfunction "1_1") (pintype "passive"))
      (node (ref "C169") (pin "1") (pinfunction "1_1") (pintype "passive"))
      (node (ref "C174") (pin "2") (pinfunction "2_2") (pintype "passive"))
      (node (ref "C177") (pin "1") (pinfunction "1_1") (pintype "passive"))
      (node (ref "C178") (pin "1") (pinfunction "1_1") (pintype "passive"))
      (node (ref "C179") (pin "1") (pinfunction "1_1") (pintype "passive"))
      (node (ref "C181") (pin "1") (pinfunction "1_1") (pintype "passive"))
      (node (ref "C182") (pin "1") (pinfunction "1_1") (pintype "passive"))
      (node (ref "C211") (pin "1") (pinfunction "1_1") (pintype "passive"))
      (node (ref "C33") (pin "1") (pinfunction "1_1") (pintype "passive"))
      (node (ref "C34") (pin "1") (pinfunction "1_1") (pintype "passive"))
      (node (ref "C35") (pin "1") (pinfunction "1_1") (pintype "passive"))
      (node (ref "C48") (pin "1") (pinfunction "1_1") (pintype "passive"))
      (node (ref "C49") (pin "1") (pinfunction "1_1") (pintype "passive"))
      (node (ref "C63") (pin "2") (pinfunction "2_2") (pintype "passive"))
      (node (ref "C64") (pin "1") (pinfunction "1_1") (pintype "passive"))
      (node (ref "C67") (pin "1") (pinfunction "1_1") (pintype "passive"))
      (node (ref "C7") (pin "1") (pinfunction "1_1") (pintype "passive"))
      (node (ref "C70") (pin "1") (pinfunction "1_1") (pintype "passive"))
      (node (ref "C73") (pin "1") (pinfunction "1_1") (pintype "passive"))
      (node (ref "C74") (pin "2") (pinfunction "2_2") (pintype "passive"))
      (node (ref "C75") (pin "1") (pinfunction "1_1") (pintype "passive"))
      (node (ref "C76") (pin "2") (pinfunction "2_2") (pintype "passive"))
      (node (ref "C77") (pin "1") (pinfunction "1_1") (pintype "passive"))
      (node (ref "C78") (pin "1") (pinfunction "1_1") (pintype "passive"))
      (node (ref "C79") (pin "1") (pinfunction "1_1") (pintype "passive"))
      (node (ref "C87") (pin "1") (pinfunction "1_1") (pintype "passive"))
      (node (ref "C92") (pin "2") (pinfunction "2_2") (pintype "passive"))
      (node (ref "D1") (pin "2") (pinfunction "A_2") (pintype "passive"))
      (node (ref "D2") (pin "1") (pinfunction "C_1") (pintype "passive"))
      (node (ref "IC12") (pin "4") (pinfunction "GND_4") (pintype "power_in"))
      (node (ref "IC12") (pin "5") (pinfunction "A2_5") (pintype "input"))
      (node (ref "IC12") (pin "6") (pinfunction "A1_6") (pintype "input"))
      (node (ref "IC12") (pin "7") (pinfunction "A0_7") (pintype "input"))
      (node (ref "IC15") (pin "B5") (pinfunction "GND_1_B5") (pintype "power_in"))
      (node (ref "IC15") (pin "C1") (pinfunction "GND_2_C1") (pintype "power_in"))
      (node (ref "IC15") (pin "C2") (pinfunction "GND_3_C2") (pintype "power_in"))
      (node (ref "IC15") (pin "C5") (pinfunction "SYNC/MODE_C5") (pintype "input"))
      (node (ref "IC15") (pin "D5") (pinfunction "GND_4_D5") (pintype "power_in"))
      (node (ref "IC18") (pin "12") (pinfunction "GND_12") (pintype "power_in"))
      (node (ref "IC18") (pin "21") (pinfunction "GND_21") (pintype "power_in"))
      (node (ref "IC21") (pin "11") (pinfunction "GND_11") (pintype "power_in"))
      (node (ref "IC21") (pin "5") (pinfunction "ILIM_5") (pintype "input"))
      (node (ref "IC21") (pin "8") (pinfunction "GND_8") (pintype "power_in"))
      (node (ref "IC22") (pin "11") (pinfunction "FSEL_11") (pintype "input"))
      (node (ref "IC22") (pin "3") (pinfunction "GND_3") (pintype "power_in"))
      (node (ref "IC22") (pin "4") (pinfunction "AGND_4") (pintype "power_in"))
      (node (ref "IC3") (pin "2") (pinfunction "GND_2") (pintype "power_in"))
      (node (ref "IC5") (pin "1") (pinfunction "GND_1") (pintype "power_in"))
      (node (ref "IC7") (pin "12") (pinfunction "GND_12") (pintype "power_in"))
      (node (ref "IC7") (pin "21") (pinfunction "GND_21") (pintype "power_in"))
      (node (ref "IC9") (pin "11") (pinfunction "GND_11") (pintype "power_in"))
      (node (ref "IC9") (pin "5") (pinfunction "ILIM_5") (pintype "input"))
      (node (ref "IC9") (pin "8") (pinfunction "GND_8") (pintype "power_in"))
      (node (ref "LD1") (pin "2") (pinfunction "A_2") (pintype "passive"))
      (node (ref "LD10") (pin "1") (pinfunction "C_1") (pintype "passive"))
      (node (ref "LD3") (pin "1") (pinfunction "C_1") (pintype "passive"))
      (node (ref "LD4") (pin "1") (pinfunction "C_1") (pintype "passive"))
      (node (ref "LD5") (pin "1") (pinfunction "C_1") (pintype "passive"))
      (node (ref "LD9") (pin "1") (pinfunction "C_1") (pintype "passive"))
      (node (ref "R130") (pin "1") (pinfunction "1_1") (pintype "passive"))
      (node (ref "R135") (pin "1") (pinfunction "1_1") (pintype "passive"))
      (node (ref "R136") (pin "1") (pinfunction "1_1") (pintype "passive"))
      (node (ref "R18") (pin "2") (pinfunction "2_2") (pintype "passive"))
      (node (ref "R55") (pin "2") (pinfunction "2_2") (pintype "passive"))
      (node (ref "R79") (pin "1") (pinfunction "1_1") (pintype "passive"))
      (node (ref "R80") (pin "1") (pinfunction "1_1") (pintype "passive"))
      (node (ref "R81") (pin "2") (pinfunction "2_2") (pintype "passive"))
      (node (ref "R82") (pin "2") (pinfunction "2_2") (pintype "passive"))
      (node (ref "R87") (pin "2") (pinfunction "2_2") (pintype "passive"))
      (node (ref "T2") (pin "2") (pinfunction "S_2") (pintype "passive"))
      (node (ref "T3") (pin "2") (pinfunction "S_2") (pintype "passive"))
    )
    (net (code "6") (name "N5V0AS") (class "Default")
      (node (ref "C35") (pin "2") (pinfunction "2_2") (pintype "passive"))
      (node (ref "D2") (pin "2") (pinfunction "A_2") (pintype "passive"))
      (node (ref "IC5") (pin "3") (pinfunction "OUT_3") (pintype "power_in"))
      (node (ref "R5") (pin "2") (pinfunction "2_2") (pintype "passive"))
      (node (ref "TP12") (pin "1") (pinfunction "1_1") (pintype "bidirectional"))
    )
    (net (code "7") (name "N12V0AS") (class "Default")
      (node (ref "C49") (pin "2") (pinfunction "2_2") (pintype "passive"))
      (node (ref "IC5") (pin "2") (pinfunction "IN_2") (pintype "input"))
      (node (ref "IC5") (pin "4") (pinfunction "IN_4") (pintype "input"))
    )
    (net (code "8") (name "Net-(IC7-FB)") (class "Default")
      (node (ref "IC7") (pin "16") (pinfunction "FB_16") (pintype "input"))
      (node (ref "R23") (pin "1") (pinfunction "1_1") (pintype "passive"))
      (node (ref "R80") (pin "2") (pinfunction "2_2") (pintype "passive"))
    )
    (net (code "9") (name "Net-(IC9-PGFB)") (class "Default")
      (node (ref "IC9") (pin "6") (pinfunction "PGFB_6") (pintype "input"))
      (node (ref "R81") (pin "1") (pinfunction "1_1") (pintype "passive"))
      (node (ref "R83") (pin "2") (pinfunction "2_2") (pintype "passive"))
    )
    (net (code "10") (name "Net-(IC9-SET)") (class "Default")
      (node (ref "C92") (pin "1") (pinfunction "1_1") (pintype "passive"))
      (node (ref "IC9") (pin "7") (pinfunction "SET_7") (pintype "input"))
      (node (ref "R75") (pin "2") (pinfunction "2_2") (pintype "passive"))
    )
    (net (code "11") (name "Net-(IC12-SCL)") (class "Default")
      (node (ref "IC12") (pin "2") (pinfunction "SCL_2") (pintype "input"))
      (node (ref "R122") (pin "1") (pinfunction "1_1") (pintype "passive"))
      (node (ref "R125") (pin "2") (pinfunction "2_2") (pintype "passive"))
    )
    (net (code "12") (name "Net-(IC12-SDA)") (class "Default")
      (node (ref "IC12") (pin "1") (pinfunction "SDA_1") (pintype "bidirectional"))
      (node (ref "R121") (pin "1") (pinfunction "1_1") (pintype "passive"))
      (node (ref "R124") (pin "2") (pinfunction "2_2") (pintype "passive"))
    )
    (net (code "13") (name "Net-(IC15-COMP1)") (class "Default")
      (node (ref "IC15") (pin "E5") (pinfunction "COMP1_E5") (pintype "passive"))
      (node (ref "TP7") (pin "1") (pinfunction "1_1") (pintype "bidirectional"))
    )
    (net (code "14") (name "Net-(IC15-COMP2)") (class "Default")
      (node (ref "IC15") (pin "A5") (pinfunction "COMP2_A5") (pintype "passive"))
      (node (ref "TP8") (pin "1") (pinfunction "1_1") (pintype "bidirectional"))
    )
    (net (code "15") (name "Net-(IC15-FB1)") (class "Default")
      (node (ref "IC15") (pin "E4") (pinfunction "FB1_E4") (pintype "input"))
      (node (ref "R55") (pin "1") (pinfunction "1_1") (pintype "passive"))
      (node (ref "R82") (pin "1") (pinfunction "1_1") (pintype "passive"))
    )
    (net (code "16") (name "Net-(IC15-FB2)") (class "Default")
      (node (ref "IC15") (pin "A4") (pinfunction "FB2_A4") (pintype "input"))
      (node (ref "R84") (pin "1") (pinfunction "1_1") (pintype "passive"))
    )
    (net (code "17") (name "Net-(IC15-FREQ)") (class "Default")
      (node (ref "IC15") (pin "C4") (pinfunction "FREQ_C4") (pintype "input"))
      (node (ref "TP6") (pin "1") (pinfunction "1_1") (pintype "bidirectional"))
    )
    (net (code "18") (name "Net-(IC15-INTVCC)") (class "Default")
      (node (ref "IC15") (pin "C3") (pinfunction "INTVCC_C3") (pintype "input"))
      (node (ref "TP5") (pin "1") (pinfunction "1_1") (pintype "bidirectional"))
    )
    (net (code "19") (name "Net-(IC15-RUN1)") (class "Default")
      (node (ref "IC15") (pin "B2") (pinfunction "RUN2_B2") (pintype "input"))
      (node (ref "IC15") (pin "D2") (pinfunction "RUN1_D2") (pintype "input"))
      (node (ref "IC22") (pin "8") (pinfunction "EN_8") (pintype "input"))
      (node (ref "R120") (pin "2") (pinfunction "2_2") (pintype "passive"))
      (node (ref "R123") (pin "2") (pinfunction "2_2") (pintype "passive"))
    )
    (net (code "20") (name "Net-(IC15-TRACK{slash}SS1)") (class "Default")
      (node (ref "C67") (pin "2") (pinfunction "2_2") (pintype "passive"))
      (node (ref "IC15") (pin "A3") (pinfunction "TRACK/SS2_A3") (pintype "input"))
      (node (ref "IC15") (pin "E3") (pinfunction "TRACK/SS1_E3") (pintype "input"))
    )
    (net (code "21") (name "Net-(IC15-VOUT1_1)") (class "Default")
      (node (ref "C73") (pin "2") (pinfunction "2_2") (pintype "passive"))
      (node (ref "IC15") (pin "D1") (pinfunction "VOUT1_1_D1") (pintype "power_in"))
      (node (ref "IC15") (pin "E1") (pinfunction "VOUT1_2_E1") (pintype "power_in"))
      (node (ref "L2") (pin "1") (pinfunction "1_1") (pintype "passive"))
    )
    (net (code "22") (name "Net-(IC15-VOUT2_1)") (class "Default")
      (node (ref "C161") (pin "2") (pinfunction "2_2") (pintype "passive"))
      (node (ref "IC15") (pin "A1") (pinfunction "VOUT2_1_A1") (pintype "power_in"))
      (node (ref "IC15") (pin "B1") (pinfunction "VOUT2_2_B1") (pintype "power_in"))
      (node (ref "L3") (pin "1") (pinfunction "1_1") (pintype "passive"))
    )
    (net (code "23") (name "Net-(IC18-FB)") (class "Default")
      (node (ref "IC18") (pin "16") (pinfunction "FB_16") (pintype "input"))
      (node (ref "R129") (pin "1") (pinfunction "1_1") (pintype "passive"))
      (node (ref "R130") (pin "2") (pinfunction "2_2") (pintype "passive"))
    )
    (net (code "24") (name "Net-(IC21-PGFB)") (class "Default")
      (node (ref "IC21") (pin "6") (pinfunction "PGFB_6") (pintype "input"))
      (node (ref "R18") (pin "1") (pinfunction "1_1") (pintype "passive"))
      (node (ref "R20") (pin "2") (pinfunction "2_2") (pintype "passive"))
    )
    (net (code "25") (name "Net-(IC21-SET)") (class "Default")
      (node (ref "C174") (pin "1") (pinfunction "1_1") (pintype "passive"))
      (node (ref "IC21") (pin "7") (pinfunction "SET_7") (pintype "input"))
      (node (ref "R133") (pin "2") (pinfunction "2_2") (pintype "passive"))
    )
    (net (code "26") (name "Net-(IC22-FB)") (class "Default")
      (node (ref "IC22") (pin "5") (pinfunction "FB_5") (pintype "input"))
      (node (ref "R134") (pin "1") (pinfunction "1_1") (pintype "passive"))
      (node (ref "R136") (pin "2") (pinfunction "2_2") (pintype "passive"))
    )
    (net (code "27") (name "Net-(IC22-MODE)") (class "Default")
      (node (ref "IC22") (pin "10") (pinfunction "MODE_10") (pintype "input"))
      (node (ref "R166") (pin "1") (pinfunction "1_1") (pintype "passive"))
    )
    (net (code "28") (name "Net-(IC22-SS{slash}TR)") (class "Default")
      (node (ref "C139") (pin "1") (pinfunction "1_1") (pintype "passive"))
      (node (ref "IC22") (pin "9") (pinfunction "SS/TR_9") (pintype "input"))
    )
    (net (code "29") (name "Net-(IC22-SW)") (class "Default")
      (node (ref "IC22") (pin "2") (pinfunction "SW_2") (pintype "output"))
      (node (ref "L4") (pin "1") (pinfunction "1_1") (pintype "passive"))
    )
    (net (code "30") (name "Net-(LD1-C)") (class "Default")
      (node (ref "LD1") (pin "1") (pinfunction "C_1") (pintype "passive"))
      (node (ref "R5") (pin "1") (pinfunction "1_1") (pintype "passive"))
    )
    (net (code "31") (name "Net-(LD3-A)") (class "Default")
      (node (ref "LD3") (pin "2") (pinfunction "A_2") (pintype "passive"))
      (node (ref "R33") (pin "1") (pinfunction "1_1") (pintype "passive"))
    )
    (net (code "32") (name "Net-(LD4-A)") (class "Default")
      (node (ref "LD4") (pin "2") (pinfunction "A_2") (pintype "passive"))
      (node (ref "R115") (pin "1") (pinfunction "1_1") (pintype "passive"))
    )
    (net (code "33") (name "Net-(LD5-A)") (class "Default")
      (node (ref "LD5") (pin "2") (pinfunction "A_2") (pintype "passive"))
      (node (ref "R116") (pin "1") (pinfunction "1_1") (pintype "passive"))
    )
    (net (code "34") (name "Net-(LD7A-A)") (class "Default")
      (node (ref "LD7") (pin "2") (pinfunction "A_2") (pintype "passive"))
      (node (ref "R38") (pin "1") (pinfunction "1_1") (pintype "passive"))
    )
    (net (code "35") (name "Net-(LD7A-C)") (class "Default")
      (node (ref "LD7") (pin "1") (pinfunction "C_1") (pintype "passive"))
      (node (ref "T3") (pin "3") (pinfunction "D_3") (pintype "passive"))
    )
    (net (code "36") (name "Net-(LD7B-A)") (class "Default")
      (node (ref "LD7") (pin "4") (pinfunction "A_4") (pintype "passive"))
      (node (ref "R143") (pin "1") (pinfunction "1_1") (pintype "passive"))
    )
    (net (code "37") (name "Net-(LD9-A)") (class "Default")
      (node (ref "LD9") (pin "2") (pinfunction "A_2") (pintype "passive"))
      (node (ref "R139") (pin "1") (pinfunction "1_1") (pintype "passive"))
    )
    (net (code "38") (name "Net-(LD10-A)") (class "Default")
      (node (ref "LD10") (pin "2") (pinfunction "A_2") (pintype "passive"))
      (node (ref "R37") (pin "1") (pinfunction "1_1") (pintype "passive"))
    )
    (net (code "39") (name "Net-(LD13-A)") (class "Default")
      (node (ref "LD13") (pin "2") (pinfunction "A_2") (pintype "passive"))
      (node (ref "R140") (pin "1") (pinfunction "1_1") (pintype "passive"))
    )
    (net (code "40") (name "Net-(LD13-C)") (class "Default")
      (node (ref "LD13") (pin "1") (pinfunction "C_1") (pintype "passive"))
      (node (ref "T2") (pin "3") (pinfunction "D_3") (pintype "passive"))
    )
    (net (code "41") (name "Net-(R75-Pad1)") (class "Default")
      (node (ref "R75") (pin "1") (pinfunction "1_1") (pintype "passive"))
      (node (ref "R79") (pin "2") (pinfunction "2_2") (pintype "passive"))
    )
    (net (code "42") (name "Net-(R84-Pad2)") (class "Default")
      (node (ref "R84") (pin "2") (pinfunction "2_2") (pintype "passive"))
      (node (ref "R87") (pin "1") (pinfunction "1_1") (pintype "passive"))
    )
    (net (code "43") (name "Net-(R133-Pad1)") (class "Default")
      (node (ref "R133") (pin "1") (pinfunction "1_1") (pintype "passive"))
      (node (ref "R135") (pin "2") (pinfunction "2_2") (pintype "passive"))
    )
    (net (code "44") (name "P1V8A") (class "Default")
      (node (ref "C169") (pin "2") (pinfunction "2_2") (pintype "passive"))
      (node (ref "IC18") (pin "1") (pinfunction "OUT_1") (pintype "power_in"))
      (node (ref "IC18") (pin "18") (pinfunction "OUT_18") (pintype "power_in"))
      (node (ref "IC18") (pin "19") (pinfunction "OUT_19") (pintype "power_in"))
      (node (ref "IC18") (pin "20") (pinfunction "OUT_20") (pintype "power_in"))
      (node (ref "R129") (pin "2") (pinfunction "2_2") (pintype "passive"))
      (node (ref "T2") (pin "1") (pinfunction "G_1") (pintype "passive"))
      (node (ref "TP10") (pin "1") (pinfunction "1_1") (pintype "bidirectional"))
    )
    (net (code "45") (name "P2V1") (class "Default")
      (node (ref "C163") (pin "2") (pinfunction "2_2") (pintype "passive"))
      (node (ref "C167") (pin "1") (pinfunction "1_1") (pintype "passive"))
      (node (ref "C76") (pin "1") (pinfunction "1_1") (pintype "passive"))
      (node (ref "IC18") (pin "5") (pinfunction "IN_5") (pintype "input"))
      (node (ref "IC18") (pin "6") (pinfunction "IN_6") (pintype "input"))
      (node (ref "IC18") (pin "7") (pinfunction "IN_7") (pintype "input"))
      (node (ref "IC18") (pin "8") (pinfunction "IN_8") (pintype "input"))
      (node (ref "L3") (pin "2") (pinfunction "2_2") (pintype "passive"))
      (node (ref "TP11") (pin "1") (pinfunction "1_1") (pintype "bidirectional"))
    )
    (net (code "46") (name "P3V3A") (class "Default")
      (node (ref "C78") (pin "2") (pinfunction "2_2") (pintype "passive"))
      (node (ref "IC7") (pin "1") (pinfunction "OUT_1") (pintype "power_in"))
      (node (ref "IC7") (pin "18") (pinfunction "OUT_18") (pintype "power_in"))
      (node (ref "IC7") (pin "19") (pinfunction "OUT_19") (pintype "power_in"))
      (node (ref "IC7") (pin "20") (pinfunction "OUT_20") (pintype "power_in"))
      (node (ref "R139") (pin "2") (pinfunction "2_2") (pintype "passive"))
      (node (ref "R23") (pin "2") (pinfunction "2_2") (pintype "passive"))
      (node (ref "TP13") (pin "1") (pinfunction "1_1") (pintype "bidirectional"))
    )
    (net (code "47") (name "P3V3s") (class "Default")
      (node (ref "C48") (pin "2") (pinfunction "2_2") (pintype "passive"))
      (node (ref "IC12") (pin "8") (pinfunction "+VS_8") (pintype "power_in"))
      (node (ref "R120") (pin "1") (pinfunction "1_1") (pintype "passive"))
      (node (ref "R121") (pin "2") (pinfunction "2_2") (pintype "passive"))
      (node (ref "R122") (pin "2") (pinfunction "2_2") (pintype "passive"))
      (node (ref "R140") (pin "2") (pinfunction "2_2") (pintype "passive"))
      (node (ref "R143") (pin "2") (pinfunction "2_2") (pintype "passive"))
      (node (ref "R38") (pin "2") (pinfunction "2_2") (pintype "passive"))
      (node (ref "R53") (pin "2") (pinfunction "2_2") (pintype "passive"))
    )
    (net (code "48") (name "P3V6") (class "Default")
      (node (ref "C63") (pin "1") (pinfunction "1_1") (pintype "passive"))
      (node (ref "C74") (pin "1") (pinfunction "1_1") (pintype "passive"))
      (node (ref "C75") (pin "2") (pinfunction "2_2") (pintype "passive"))
      (node (ref "IC7") (pin "5") (pinfunction "IN_5") (pintype "input"))
      (node (ref "IC7") (pin "6") (pinfunction "IN_6") (pintype "input"))
      (node (ref "IC7") (pin "7") (pinfunction "IN_7") (pintype "input"))
      (node (ref "IC7") (pin "8") (pinfunction "IN_8") (pintype "input"))
      (node (ref "L2") (pin "2") (pinfunction "2_2") (pintype "passive"))
      (node (ref "TP15") (pin "1") (pinfunction "1_1") (pintype "bidirectional"))
    )
    (net (code "49") (name "P5V0A") (class "Default")
      (node (ref "C117") (pin "2") (pinfunction "2_2") (pintype "passive"))
      (node (ref "C168") (pin "2") (pinfunction "2_2") (pintype "passive"))
      (node (ref "C77") (pin "2") (pinfunction "2_2") (pintype "passive"))
      (node (ref "C79") (pin "2") (pinfunction "2_2") (pintype "passive"))
      (node (ref "C87") (pin "2") (pinfunction "2_2") (pintype "passive"))
      (node (ref "IC18") (pin "10") (pinfunction "BIAS_10") (pintype "input"))
      (node (ref "IC18") (pin "11") (pinfunction "EN_11") (pintype "input"))
      (node (ref "IC7") (pin "10") (pinfunction "BIAS_10") (pintype "input"))
      (node (ref "IC7") (pin "11") (pinfunction "EN_11") (pintype "input"))
      (node (ref "IC9") (pin "10") (pinfunction "OUT_10") (pintype "output"))
      (node (ref "IC9") (pin "9") (pinfunction "OUTS_9") (pintype "output"))
      (node (ref "R115") (pin "2") (pinfunction "2_2") (pintype "passive"))
      (node (ref "R83") (pin "1") (pinfunction "1_1") (pintype "passive"))
      (node (ref "TP16") (pin "1") (pinfunction "1_1") (pintype "bidirectional"))
    )
    (net (code "50") (name "P5V0AS") (class "Default")
      (node (ref "C33") (pin "2") (pinfunction "2_2") (pintype "passive"))
      (node (ref "D1") (pin "1") (pinfunction "C_1") (pintype "passive"))
      (node (ref "IC3") (pin "1") (pinfunction "OUT_1") (pintype "power_in"))
      (node (ref "R37") (pin "2") (pinfunction "2_2") (pintype "passive"))
      (node (ref "TP19") (pin "1") (pinfunction "1_1") (pintype "bidirectional"))
    )
    (net (code "51") (name "P7V0A") (class "Default")
      (node (ref "C118") (pin "2") (pinfunction "2_2") (pintype "passive"))
      (node (ref "C155") (pin "2") (pinfunction "2_2") (pintype "passive"))
      (node (ref "C177") (pin "2") (pinfunction "2_2") (pintype "passive"))
      (node (ref "IC21") (pin "10") (pinfunction "OUT_10") (pintype "output"))
      (node (ref "IC21") (pin "9") (pinfunction "OUTS_9") (pintype "output"))
      (node (ref "R116") (pin "2") (pinfunction "2_2") (pintype "passive"))
      (node (ref "R20") (pin "1") (pinfunction "1_1") (pintype "passive"))
      (node (ref "TP17") (pin "1") (pinfunction "1_1") (pintype "bidirectional"))
    )
    (net (code "52") (name "P7V5") (class "Default")
      (node (ref "C178") (pin "2") (pinfunction "2_2") (pintype "passive"))
      (node (ref "C179") (pin "2") (pinfunction "2_2") (pintype "passive"))
      (node (ref "C211") (pin "2") (pinfunction "2_2") (pintype "passive"))
      (node (ref "IC22") (pin "6") (pinfunction "VOS_6") (pintype "input"))
      (node (ref "L4") (pin "2") (pinfunction "2_2") (pintype "passive"))
      (node (ref "L5") (pin "1") (pinfunction "1_1") (pintype "passive"))
      (node (ref "R134") (pin "2") (pinfunction "2_2") (pintype "passive"))
    )
    (net (code "53") (name "P7V5A") (class "Default")
      (node (ref "C132") (pin "2") (pinfunction "2_2") (pintype "passive"))
      (node (ref "C156") (pin "1") (pinfunction "1_1") (pintype "passive"))
      (node (ref "C7") (pin "2") (pinfunction "2_2") (pintype "passive"))
      (node (ref "IC21") (pin "1") (pinfunction "IN_1") (pintype "input"))
      (node (ref "IC21") (pin "2") (pinfunction "IN_2") (pintype "input"))
      (node (ref "IC21") (pin "3") (pinfunction "EN/UV_3") (pintype "input"))
      (node (ref "IC9") (pin "1") (pinfunction "IN_1") (pintype "input"))
      (node (ref "IC9") (pin "2") (pinfunction "IN_2") (pintype "input"))
      (node (ref "IC9") (pin "3") (pinfunction "EN/UV_3") (pintype "input"))
      (node (ref "L5") (pin "2") (pinfunction "2_2") (pintype "passive"))
    )
    (net (code "54") (name "P12V0") (class "Default")
      (node (ref "C181") (pin "2") (pinfunction "2_2") (pintype "passive"))
      (node (ref "C182") (pin "2") (pinfunction "2_2") (pintype "passive"))
      (node (ref "C64") (pin "2") (pinfunction "2_2") (pintype "passive"))
      (node (ref "C70") (pin "2") (pinfunction "2_2") (pintype "passive"))
      (node (ref "IC15") (pin "A2") (pinfunction "VIN_1_A2") (pintype "power_in"))
      (node (ref "IC15") (pin "B3") (pinfunction "VIN_2_B3") (pintype "power_in"))
      (node (ref "IC15") (pin "D3") (pinfunction "VIN_3_D3") (pintype "power_in"))
      (node (ref "IC15") (pin "E2") (pinfunction "VIN_4_E2") (pintype "power_in"))
      (node (ref "IC22") (pin "1") (pinfunction "VIN_1") (pintype "input"))
      (node (ref "R166") (pin "2") (pinfunction "2_2") (pintype "passive"))
      (node (ref "R33") (pin "2") (pinfunction "2_2") (pintype "passive"))
      (node (ref "TP18") (pin "1") (pinfunction "1_1") (pintype "bidirectional"))
    )
    (net (code "55") (name "P12V0AS") (class "Default")
      (node (ref "C34") (pin "2") (pinfunction "2_2") (pintype "passive"))
      (node (ref "IC3") (pin "3") (pinfunction "IN_3") (pintype "input"))
    )
    (net (code "56") (name "unconnected-(IC7-NC-Pad2)") (class "Default")
      (node (ref "IC7") (pin "2") (pinfunction "NC_2") (pintype "passive+no_connect"))
    )
    (net (code "57") (name "unconnected-(IC7-NC-Pad3)") (class "Default")
      (node (ref "IC7") (pin "3") (pinfunction "NC_3") (pintype "passive+no_connect"))
    )
    (net (code "58") (name "unconnected-(IC7-NC-Pad4)") (class "Default")
      (node (ref "IC7") (pin "4") (pinfunction "NC_4") (pintype "passive+no_connect"))
    )
    (net (code "59") (name "unconnected-(IC7-NC-Pad13)") (class "Default")
      (node (ref "IC7") (pin "13") (pinfunction "NC_13") (pintype "passive+no_connect"))
    )
    (net (code "60") (name "unconnected-(IC7-NC-Pad14)") (class "Default")
      (node (ref "IC7") (pin "14") (pinfunction "NC_14") (pintype "passive+no_connect"))
    )
    (net (code "61") (name "unconnected-(IC7-NC-Pad17)") (class "Default")
      (node (ref "IC7") (pin "17") (pinfunction "NC_17") (pintype "passive+no_connect"))
    )
    (net (code "62") (name "unconnected-(IC7-SS-Pad15)") (class "Default")
      (node (ref "IC7") (pin "15") (pinfunction "SS_15") (pintype "output+no_connect"))
    )
    (net (code "63") (name "unconnected-(IC18-NC-Pad2)") (class "Default")
      (node (ref "IC18") (pin "2") (pinfunction "NC_2") (pintype "passive+no_connect"))
    )
    (net (code "64") (name "unconnected-(IC18-NC-Pad3)") (class "Default")
      (node (ref "IC18") (pin "3") (pinfunction "NC_3") (pintype "passive+no_connect"))
    )
    (net (code "65") (name "unconnected-(IC18-NC-Pad4)") (class "Default")
      (node (ref "IC18") (pin "4") (pinfunction "NC_4") (pintype "passive+no_connect"))
    )
    (net (code "66") (name "unconnected-(IC18-NC-Pad13)") (class "Default")
      (node (ref "IC18") (pin "13") (pinfunction "NC_13") (pintype "passive+no_connect"))
    )
    (net (code "67") (name "unconnected-(IC18-NC-Pad14)") (class "Default")
      (node (ref "IC18") (pin "14") (pinfunction "NC_14") (pintype "passive+no_connect"))
    )
    (net (code "68") (name "unconnected-(IC18-NC-Pad17)") (class "Default")
      (node (ref "IC18") (pin "17") (pinfunction "NC_17") (pintype "passive+no_connect"))
    )
    (net (code "69") (name "unconnected-(IC18-SS-Pad15)") (class "Default")
      (node (ref "IC18") (pin "15") (pinfunction "SS_15") (pintype "output+no_connect"))
    )
  )
)
